# rapidshark_mark_6_2.net
KiCad netlist of a schematic drawn in EAGLE
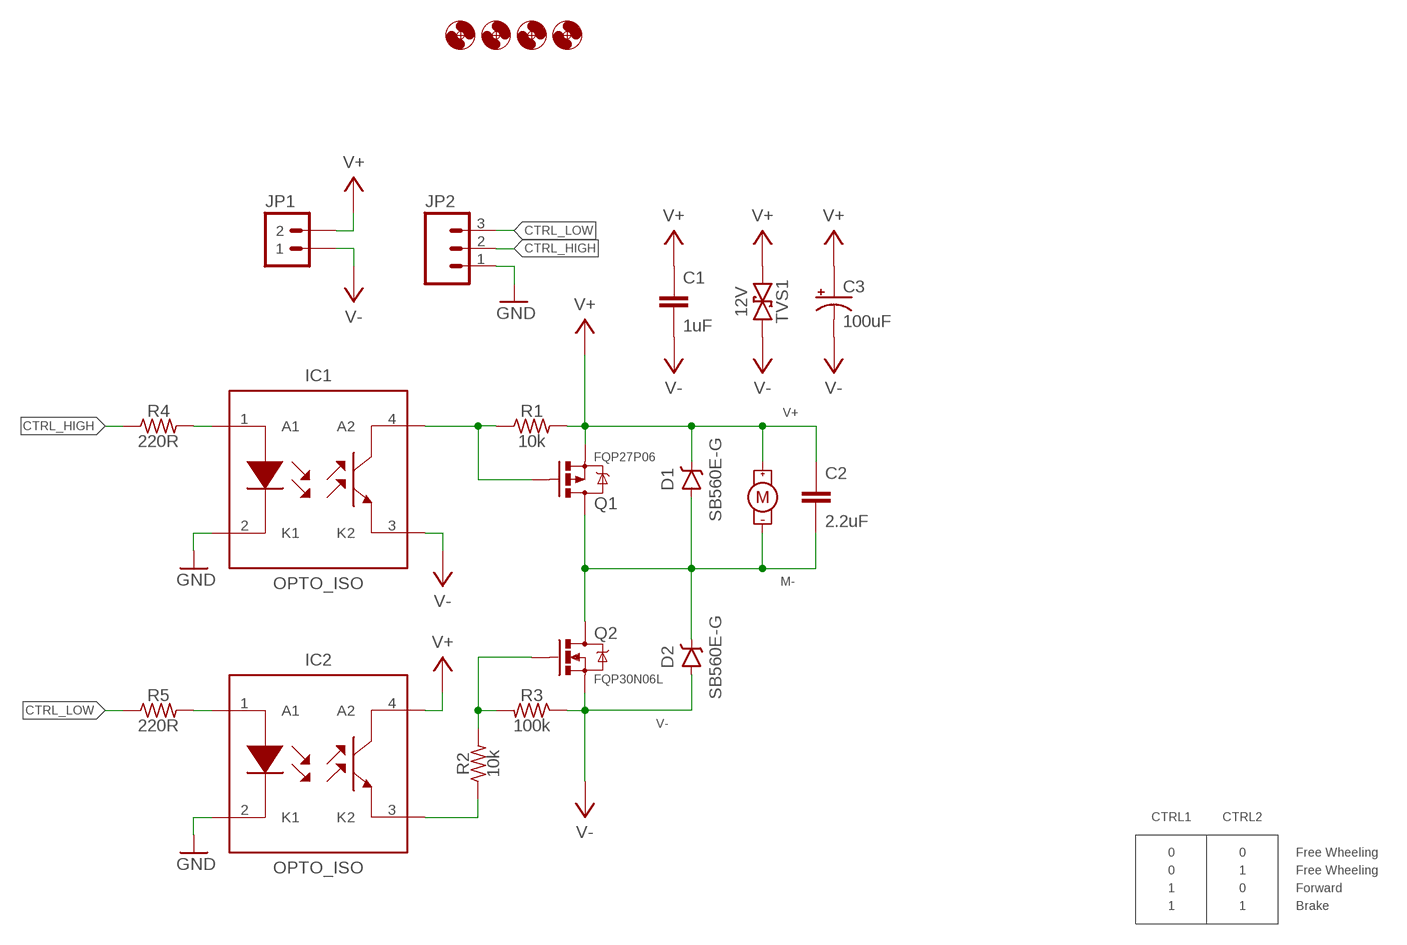
[diagram p0: schematic, sheet 1]

(export (version "E")
  (design (tool "Eeschema 10.0.6"))
  (components
    (comp (ref "C1")
      (value "1uF")
      (footprint "eagle-import:C025-024X044")
      (libsource (lib "eagle-import") (part "CAPACITOR-CERAMIC025-024X044"))
    )
    (comp (ref "C2")
      (value "2.2uF")
      (footprint "eagle-import:C050-025X075")
      (libsource (lib "eagle-import") (part "CAPACITOR-CERAMIC050-025X075"))
    )
    (comp (ref "C3")
      (value "100uF")
      (footprint "eagle-import:E2.5-6-FLAT")
      (libsource (lib "eagle-import") (part "CAPACITOR-POLARIZEDE2.5-6-FLAT"))
    )
    (comp (ref "D1")
      (value "SB560E-G")
      (footprint "eagle-import:DIODE-12.70MM-FAT")
      (libsource (lib "eagle-import") (part "DIODE-SCHOTTKYPTH-12.70-FAT"))
    )
    (comp (ref "D2")
      (value "SB560E-G")
      (footprint "eagle-import:DIODE-12.70MM-FAT")
      (libsource (lib "eagle-import") (part "DIODE-SCHOTTKYPTH-12.70-FAT"))
    )
    (comp (ref "H1")
      (value "HOLE#2")
      (footprint "eagle-import:HOLE-#2")
      (libsource (lib "eagle-import") (part "HOLE#2"))
    )
    (comp (ref "H2")
      (value "HOLE#2")
      (footprint "eagle-import:HOLE-#2")
      (libsource (lib "eagle-import") (part "HOLE#2"))
    )
    (comp (ref "H3")
      (value "HOLE#2")
      (footprint "eagle-import:HOLE-#2")
      (libsource (lib "eagle-import") (part "HOLE#2"))
    )
    (comp (ref "H4")
      (value "HOLE#2")
      (footprint "eagle-import:HOLE-#2")
      (libsource (lib "eagle-import") (part "HOLE#2"))
    )
    (comp (ref "IC1")
      (value "OPTO_ISO")
      (footprint "eagle-import:DIL04")
      (libsource (lib "eagle-import") (part "OPTOISOLATORDIP4"))
    )
    (comp (ref "IC2")
      (value "OPTO_ISO")
      (footprint "eagle-import:DIL04")
      (libsource (lib "eagle-import") (part "OPTOISOLATORDIP4"))
    )
    (comp (ref "JP1")
      (value "M02PTH4")
      (footprint "eagle-import:1X02_XTRA_BIG")
      (libsource (lib "eagle-import") (part "M02PTH4"))
    )
    (comp (ref "JP2")
      (value "M03JST-PTH")
      (footprint "eagle-import:JST-3-PH-RA-PTH")
      (libsource (lib "eagle-import") (part "M03JST-PTH"))
    )
    (comp (ref "M1")
      (value "MOTORXTRA-BIG")
      (footprint "eagle-import:1X02_XTRA_BIG")
      (libsource (lib "eagle-import") (part "MOTORXTRA-BIG"))
    )
    (comp (ref "Q1")
      (value "FQP27P06")
      (footprint "eagle-import:TO-220-SIDE-THERM-ALT")
      (libsource (lib "eagle-import") (part "MOSFET-PCHANNELFQP27P06-FLAT"))
    )
    (comp (ref "Q2")
      (value "FQP30N06L")
      (footprint "eagle-import:TO-220-SIDE-THERM-ALT")
      (libsource (lib "eagle-import") (part "MOSFET-NCHANNELFQP30N06L-THERM"))
    )
    (comp (ref "R1")
      (value "10k")
      (footprint "eagle-import:RESISTOR-AXIAL-PTH-7.62MM")
      (libsource (lib "eagle-import") (part "RESISTORPTH-AXIAL-7.62MM"))
    )
    (comp (ref "R2")
      (value "10k")
      (footprint "eagle-import:RESISTOR-AXIAL-PTH-7.62MM")
      (libsource (lib "eagle-import") (part "RESISTORPTH-AXIAL-7.62MM"))
    )
    (comp (ref "R3")
      (value "100k")
      (footprint "eagle-import:RESISTOR-AXIAL-PTH-7.62MM")
      (libsource (lib "eagle-import") (part "RESISTORPTH-AXIAL-7.62MM"))
    )
    (comp (ref "R4")
      (value "220R")
      (footprint "eagle-import:RESISTOR-AXIAL-PTH-6.35MM")
      (libsource (lib "eagle-import") (part "RESISTORPTH-AXIAL-6.35MM"))
    )
    (comp (ref "R5")
      (value "220R")
      (footprint "eagle-import:RESISTOR-AXIAL-PTH-6.35MM")
      (libsource (lib "eagle-import") (part "RESISTORPTH-AXIAL-6.35MM"))
    )
    (comp (ref "TVS1")
      (value "12V")
      (footprint "eagle-import:DO-41-TVS-BI-10.16MM")
      (libsource (lib "eagle-import") (part "TVSDO-41-10.16MM"))
    )
  )
  (nets
    (net (code "1") (name "/M-") (class "Default")
      (node (ref "C2") (pin "2") (pinfunction "2_2") (pintype "passive"))
      (node (ref "D1") (pin "A") (pinfunction "A_A") (pintype "passive"))
      (node (ref "D2") (pin "K") (pinfunction "C_K") (pintype "passive"))
      (node (ref "M1") (pin "2") (pinfunction "-_2") (pintype "bidirectional"))
      (node (ref "Q1") (pin "2") (pinfunction "D_2") (pintype "passive"))
      (node (ref "Q1") (pin "GND@1") (pinfunction "D_GND@1") (pintype "passive"))
      (node (ref "Q1") (pin "GND@10") (pinfunction "D_GND@10") (pintype "passive"))
      (node (ref "Q1") (pin "GND@11") (pinfunction "D_GND@11") (pintype "passive"))
      (node (ref "Q1") (pin "GND@12") (pinfunction "D_GND@12") (pintype "passive"))
      (node (ref "Q1") (pin "GND@13") (pinfunction "D_GND@13") (pintype "passive"))
      (node (ref "Q1") (pin "GND@14") (pinfunction "D_GND@14") (pintype "passive"))
      (node (ref "Q1") (pin "GND@15") (pinfunction "D_GND@15") (pintype "passive"))
      (node (ref "Q1") (pin "GND@16") (pinfunction "D_GND@16") (pintype "passive"))
      (node (ref "Q1") (pin "GND@17") (pinfunction "D_GND@17") (pintype "passive"))
      (node (ref "Q1") (pin "GND@18") (pinfunction "D_GND@18") (pintype "passive"))
      (node (ref "Q1") (pin "GND@19") (pinfunction "D_GND@19") (pintype "passive"))
      (node (ref "Q1") (pin "GND@2") (pinfunction "D_GND@2") (pintype "passive"))
      (node (ref "Q1") (pin "GND@20") (pinfunction "D_GND@20") (pintype "passive"))
      (node (ref "Q1") (pin "GND@21") (pinfunction "D_GND@21") (pintype "passive"))
      (node (ref "Q1") (pin "GND@22") (pinfunction "D_GND@22") (pintype "passive"))
      (node (ref "Q1") (pin "GND@23") (pinfunction "D_GND@23") (pintype "passive"))
      (node (ref "Q1") (pin "GND@24") (pinfunction "D_GND@24") (pintype "passive"))
      (node (ref "Q1") (pin "GND@25") (pinfunction "D_GND@25") (pintype "passive"))
      (node (ref "Q1") (pin "GND@26") (pinfunction "D_GND@26") (pintype "passive"))
      (node (ref "Q1") (pin "GND@27") (pinfunction "D_GND@27") (pintype "passive"))
      (node (ref "Q1") (pin "GND@3") (pinfunction "D_GND@3") (pintype "passive"))
      (node (ref "Q1") (pin "GND@4") (pinfunction "D_GND@4") (pintype "passive"))
      (node (ref "Q1") (pin "GND@5") (pinfunction "D_GND@5") (pintype "passive"))
      (node (ref "Q1") (pin "GND@6") (pinfunction "D_GND@6") (pintype "passive"))
      (node (ref "Q1") (pin "GND@7") (pinfunction "D_GND@7") (pintype "passive"))
      (node (ref "Q1") (pin "GND@8") (pinfunction "D_GND@8") (pintype "passive"))
      (node (ref "Q1") (pin "GND@9") (pinfunction "D_GND@9") (pintype "passive"))
      (node (ref "Q2") (pin "2") (pinfunction "D_2") (pintype "passive"))
      (node (ref "Q2") (pin "GND@1") (pinfunction "D_GND@1") (pintype "passive"))
      (node (ref "Q2") (pin "GND@10") (pinfunction "D_GND@10") (pintype "passive"))
      (node (ref "Q2") (pin "GND@11") (pinfunction "D_GND@11") (pintype "passive"))
      (node (ref "Q2") (pin "GND@12") (pinfunction "D_GND@12") (pintype "passive"))
      (node (ref "Q2") (pin "GND@13") (pinfunction "D_GND@13") (pintype "passive"))
      (node (ref "Q2") (pin "GND@14") (pinfunction "D_GND@14") (pintype "passive"))
      (node (ref "Q2") (pin "GND@15") (pinfunction "D_GND@15") (pintype "passive"))
      (node (ref "Q2") (pin "GND@16") (pinfunction "D_GND@16") (pintype "passive"))
      (node (ref "Q2") (pin "GND@17") (pinfunction "D_GND@17") (pintype "passive"))
      (node (ref "Q2") (pin "GND@18") (pinfunction "D_GND@18") (pintype "passive"))
      (node (ref "Q2") (pin "GND@19") (pinfunction "D_GND@19") (pintype "passive"))
      (node (ref "Q2") (pin "GND@2") (pinfunction "D_GND@2") (pintype "passive"))
      (node (ref "Q2") (pin "GND@20") (pinfunction "D_GND@20") (pintype "passive"))
      (node (ref "Q2") (pin "GND@21") (pinfunction "D_GND@21") (pintype "passive"))
      (node (ref "Q2") (pin "GND@22") (pinfunction "D_GND@22") (pintype "passive"))
      (node (ref "Q2") (pin "GND@23") (pinfunction "D_GND@23") (pintype "passive"))
      (node (ref "Q2") (pin "GND@24") (pinfunction "D_GND@24") (pintype "passive"))
      (node (ref "Q2") (pin "GND@25") (pinfunction "D_GND@25") (pintype "passive"))
      (node (ref "Q2") (pin "GND@26") (pinfunction "D_GND@26") (pintype "passive"))
      (node (ref "Q2") (pin "GND@27") (pinfunction "D_GND@27") (pintype "passive"))
      (node (ref "Q2") (pin "GND@3") (pinfunction "D_GND@3") (pintype "passive"))
      (node (ref "Q2") (pin "GND@4") (pinfunction "D_GND@4") (pintype "passive"))
      (node (ref "Q2") (pin "GND@5") (pinfunction "D_GND@5") (pintype "passive"))
      (node (ref "Q2") (pin "GND@6") (pinfunction "D_GND@6") (pintype "passive"))
      (node (ref "Q2") (pin "GND@7") (pinfunction "D_GND@7") (pintype "passive"))
      (node (ref "Q2") (pin "GND@8") (pinfunction "D_GND@8") (pintype "passive"))
      (node (ref "Q2") (pin "GND@9") (pinfunction "D_GND@9") (pintype "passive"))
    )
    (net (code "2") (name "CTRL_HIGH") (class "Default")
      (node (ref "JP2") (pin "2") (pinfunction "2_2") (pintype "passive"))
      (node (ref "R4") (pin "P$1") (pinfunction "1_P$1") (pintype "passive"))
    )
    (net (code "3") (name "CTRL_LOW") (class "Default")
      (node (ref "JP2") (pin "3") (pinfunction "3_3") (pintype "passive"))
      (node (ref "R5") (pin "P$1") (pinfunction "1_P$1") (pintype "passive"))
    )
    (net (code "4") (name "GND") (class "Default")
      (node (ref "IC1") (pin "2") (pinfunction "K1_2") (pintype "bidirectional"))
      (node (ref "IC2") (pin "2") (pinfunction "K1_2") (pintype "bidirectional"))
      (node (ref "JP2") (pin "1") (pinfunction "1_1") (pintype "passive"))
    )
    (net (code "5") (name "Net-(IC1-A1)") (class "Default")
      (node (ref "IC1") (pin "1") (pinfunction "A1_1") (pintype "bidirectional"))
      (node (ref "R4") (pin "P$2") (pinfunction "2_P$2") (pintype "passive"))
    )
    (net (code "6") (name "Net-(IC1-A2)") (class "Default")
      (node (ref "IC1") (pin "4") (pinfunction "A2_4") (pintype "bidirectional"))
      (node (ref "Q1") (pin "1") (pinfunction "G_1") (pintype "passive"))
      (node (ref "R1") (pin "P$1") (pinfunction "1_P$1") (pintype "passive"))
    )
    (net (code "7") (name "Net-(IC2-A1)") (class "Default")
      (node (ref "IC2") (pin "1") (pinfunction "A1_1") (pintype "bidirectional"))
      (node (ref "R5") (pin "P$2") (pinfunction "2_P$2") (pintype "passive"))
    )
    (net (code "8") (name "Net-(IC2-K2)") (class "Default")
      (node (ref "IC2") (pin "3") (pinfunction "K2_3") (pintype "bidirectional"))
      (node (ref "R2") (pin "P$1") (pinfunction "1_P$1") (pintype "passive"))
    )
    (net (code "9") (name "Net-(Q2-G)") (class "Default")
      (node (ref "Q2") (pin "1") (pinfunction "G_1") (pintype "passive"))
      (node (ref "R2") (pin "P$2") (pinfunction "2_P$2") (pintype "passive"))
      (node (ref "R3") (pin "P$2") (pinfunction "2_P$2") (pintype "passive"))
    )
    (net (code "10") (name "V+") (class "Default")
      (node (ref "C1") (pin "1") (pinfunction "1_1") (pintype "passive"))
      (node (ref "C2") (pin "1") (pinfunction "1_1") (pintype "passive"))
      (node (ref "C3") (pin "+") (pinfunction "+_+") (pintype "passive"))
      (node (ref "D1") (pin "K") (pinfunction "C_K") (pintype "passive"))
      (node (ref "IC2") (pin "4") (pinfunction "A2_4") (pintype "bidirectional"))
      (node (ref "JP1") (pin "2") (pinfunction "2_2") (pintype "passive"))
      (node (ref "M1") (pin "1") (pinfunction "+_1") (pintype "bidirectional"))
      (node (ref "Q1") (pin "3") (pinfunction "S_3") (pintype "passive"))
      (node (ref "R1") (pin "P$2") (pinfunction "2_P$2") (pintype "passive"))
      (node (ref "TVS1") (pin "P$1") (pinfunction "1_P$1") (pintype "passive"))
    )
    (net (code "11") (name "V-") (class "Default")
      (node (ref "C1") (pin "2") (pinfunction "2_2") (pintype "passive"))
      (node (ref "C3") (pin "-") (pinfunction "-_-") (pintype "passive"))
      (node (ref "D2") (pin "A") (pinfunction "A_A") (pintype "passive"))
      (node (ref "IC1") (pin "3") (pinfunction "K2_3") (pintype "bidirectional"))
      (node (ref "JP1") (pin "1") (pinfunction "1_1") (pintype "passive"))
      (node (ref "Q2") (pin "3") (pinfunction "S_3") (pintype "passive"))
      (node (ref "R3") (pin "P$1") (pinfunction "1_P$1") (pintype "passive"))
      (node (ref "TVS1") (pin "P$2") (pinfunction "2_P$2") (pintype "passive"))
    )
  )
)
